# Voltmeter_schematic.net
KiCad netlist of a schematic drawn in Altium Designer
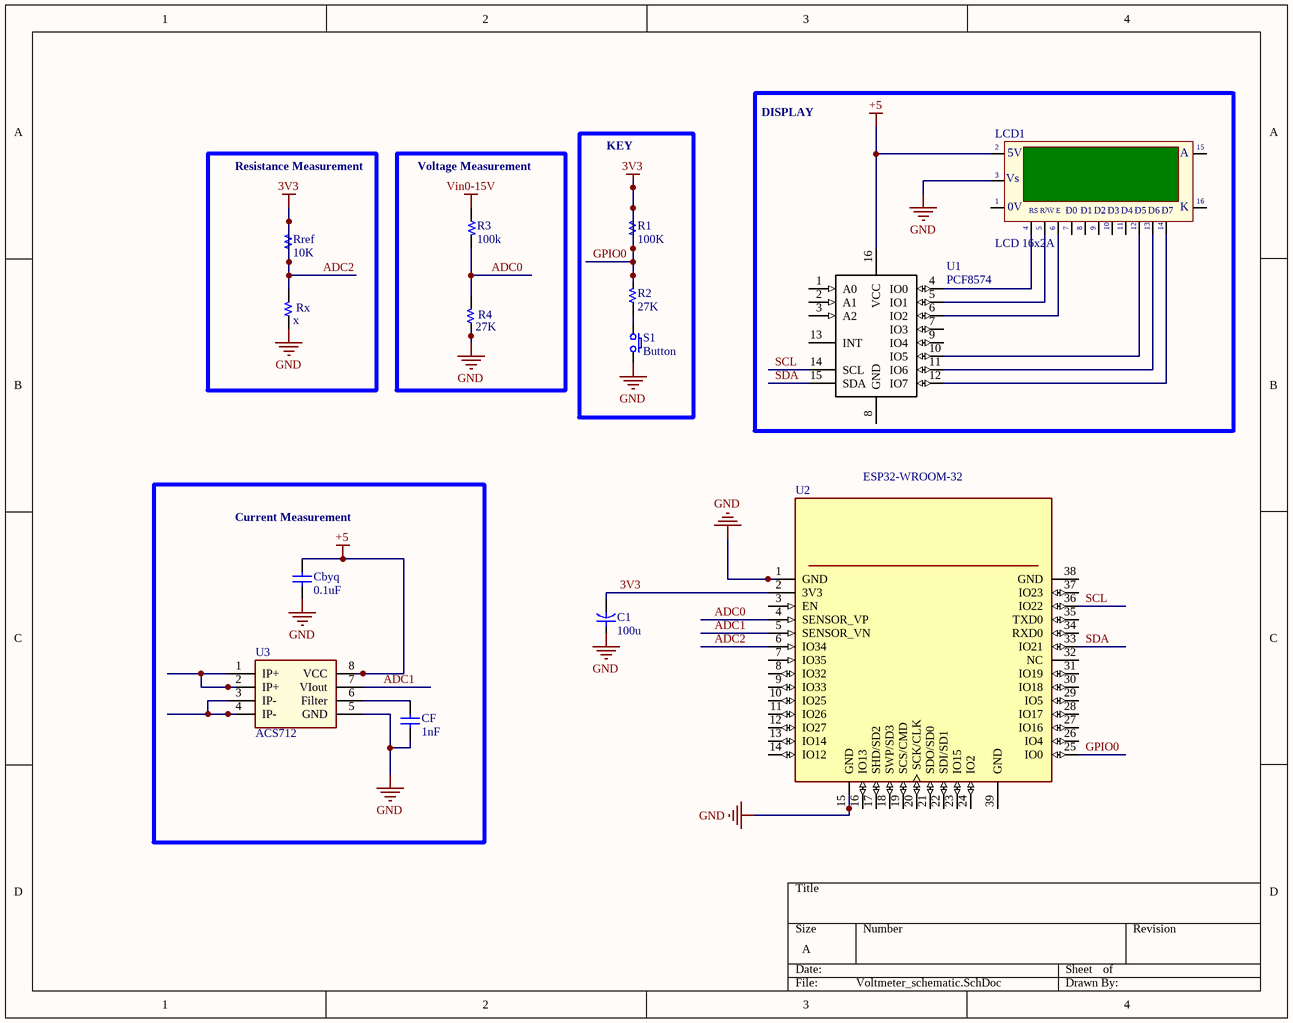
[diagram p0: Voltmeter_schematic.SchDoc]

(export (version "E")
  (design (tool "Eeschema 10.0.6"))
  (components
    (comp (ref "C1")
      (value "100u")
      (footprint "C Super Case A")
      (description "Capacitor pol")
      (libsource (lib "chipfc_libs") (part "Capacitor"))
    )
    (comp (ref "Cbyq")
      (value "0.1uF")
      (footprint "C 0805")
      (description "Capacitor non-pol")
      (libsource (lib "chipfc_libs") (part "Capacitor NP"))
    )
    (comp (ref "CF")
      (value "1nF")
      (footprint "C 0805")
      (description "Capacitor non-pol")
      (libsource (lib "chipfc_libs") (part "Capacitor NP"))
    )
    (comp (ref "LCD1")
      (value "LCD 16x2A")
      (footprint "JP16-C1T")
      (description "LCD dipslay 16 char, 2 line")
      (libsource (lib "LIBRARY") (part "LCD16x2A"))
    )
    (comp (ref "R1")
      (value "100K")
      (footprint "R 0805")
      (description "Resistor")
      (libsource (lib "chipfc_libs") (part "Resistor"))
    )
    (comp (ref "R2")
      (value "27K")
      (footprint "R 0805")
      (description "Resistor")
      (libsource (lib "chipfc_libs") (part "Resistor"))
    )
    (comp (ref "R3")
      (value "100k")
      (footprint "R 0805")
      (description "Resistor")
      (libsource (lib "chipfc_libs") (part "Resistor"))
    )
    (comp (ref "R4")
      (value "27K")
      (footprint "R 0805")
      (description "Resistor")
      (libsource (lib "chipfc_libs") (part "Resistor"))
    )
    (comp (ref "Rref")
      (value "10K")
      (footprint "R 0805")
      (description "Resistor")
      (libsource (lib "chipfc_libs") (part "Resistor"))
    )
    (comp (ref "Rx")
      (value "x")
      (footprint "R 0805")
      (description "Resistor")
      (libsource (lib "chipfc_libs") (part "Resistor"))
    )
    (comp (ref "S1")
      (value "Button")
      (footprint "SW/2/DIP")
      (description "Tact switch 2 pin")
      (libsource (lib "chipfc_libs") (part "SW SPST"))
    )
    (comp (ref "U1")
      (value "PCF8574")
      (footprint "DIP16")
      (description "I2C PORT EXPANDER")
      (fields
        (field (name "MANUFACTURER PART NUMBER") "PCF8574T/3,512")
        (field (name "MANUFACTURER") "NXP Semiconductors")
      )
      (libsource (lib "LIBRARY") (part "PCF8574"))
    )
    (comp (ref "U2")
      (value "ESP32-WROOM-32")
      (footprint "MODULE_ESP32-WROOM-32")
      (fields (field (name "MF") "Espressif Systems") (field (name "MP") "ESP32-WROOM-32D"))
      (libsource (lib "ESP32") (part "ESP32-WROOM-32"))
    )
    (comp (ref "U3") (value "ACS712") (footprint "SOIC-8") (libsource (lib "chipfc_libs") (part "ACS712")))
  )
  (nets
    (net (code "1") (name "+5") (class "Default")
      (node (ref "Cbyq") (pin "1") (pinfunction "1_1") (pintype "passive"))
      (node (ref "LCD1") (pin "2") (pinfunction "VDD_2") (pintype "passive"))
      (node (ref "U1") (pin "16") (pinfunction "VCC_16") (pintype "passive"))
      (node (ref "U3") (pin "8") (pinfunction "VCC_8") (pintype "passive"))
    )
    (net (code "2") (name "/ADC0") (class "Default")
      (node (ref "R3") (pin "2") (pinfunction "2_2") (pintype "passive"))
      (node (ref "R4") (pin "2") (pinfunction "2_2") (pintype "passive"))
      (node (ref "U2") (pin "4") (pinfunction "SENSOR_VP_4") (pintype "input"))
    )
    (net (code "3") (name "/ADC1") (class "Default")
      (node (ref "U2") (pin "5") (pinfunction "SENSOR_VN_5") (pintype "input"))
      (node (ref "U3") (pin "7") (pinfunction "VIout_7") (pintype "passive"))
    )
    (net (code "4") (name "/SCL") (class "Default")
      (node (ref "U1") (pin "14") (pinfunction "SCL_14") (pintype "open_collector"))
      (node (ref "U2") (pin "36") (pinfunction "IO22_36") (pintype "bidirectional"))
    )
    (net (code "5") (name "/SDA") (class "Default")
      (node (ref "U1") (pin "15") (pinfunction "SDA_15") (pintype "open_collector"))
      (node (ref "U2") (pin "33") (pinfunction "IO21_33") (pintype "bidirectional"))
    )
    (net (code "6") (name "3V3") (class "Default")
      (node (ref "C1") (pin "2") (pinfunction "2_2") (pintype "passive"))
      (node (ref "R1") (pin "1") (pinfunction "1_1") (pintype "passive"))
      (node (ref "R1") (pin "2") (pinfunction "2_2") (pintype "passive"))
      (node (ref "R2") (pin "2") (pinfunction "2_2") (pintype "passive"))
      (node (ref "Rref") (pin "1") (pinfunction "1_1") (pintype "passive"))
      (node (ref "Rref") (pin "2") (pinfunction "2_2") (pintype "passive"))
      (node (ref "Rx") (pin "2") (pinfunction "2_2") (pintype "passive"))
      (node (ref "U2") (pin "2") (pinfunction "3V3_2") (pintype "power_in"))
      (node (ref "U2") (pin "25") (pinfunction "IO0_25") (pintype "bidirectional"))
      (node (ref "U2") (pin "6") (pinfunction "IO34_6") (pintype "input"))
    )
    (net (code "7") (name "GND") (class "Default")
      (node (ref "CF") (pin "2") (pinfunction "2_2") (pintype "passive"))
      (node (ref "Cbyq") (pin "2") (pinfunction "2_2") (pintype "passive"))
      (node (ref "LCD1") (pin "3") (pinfunction "VEE_3") (pintype "passive"))
      (node (ref "R4") (pin "1") (pinfunction "1_1") (pintype "passive"))
      (node (ref "Rx") (pin "1") (pinfunction "1_1") (pintype "passive"))
      (node (ref "S1") (pin "2") (pinfunction "2_2") (pintype "passive"))
      (node (ref "U2") (pin "1") (pinfunction "GND_1") (pintype "power_in"))
      (node (ref "U2") (pin "15") (pinfunction "GND_15") (pintype "power_in"))
      (node (ref "U3") (pin "5") (pinfunction "GND_5") (pintype "passive"))
    )
    (net (code "8") (name "Net-(LCD1-D5)") (class "Default")
      (node (ref "LCD1") (pin "12") (pinfunction "D5_12") (pintype "passive"))
      (node (ref "U1") (pin "10") (pinfunction "IO5_10") (pintype "bidirectional"))
    )
    (net (code "9") (name "Net-(LCD1-D6)") (class "Default")
      (node (ref "LCD1") (pin "13") (pinfunction "D6_13") (pintype "passive"))
      (node (ref "U1") (pin "11") (pinfunction "IO6_11") (pintype "bidirectional"))
    )
    (net (code "10") (name "Net-(LCD1-D7)") (class "Default")
      (node (ref "LCD1") (pin "14") (pinfunction "D7_14") (pintype "passive"))
      (node (ref "U1") (pin "12") (pinfunction "IO7_12") (pintype "bidirectional"))
    )
    (net (code "11") (name "Net-(LCD1-RS)") (class "Default")
      (node (ref "LCD1") (pin "4") (pinfunction "RS_4") (pintype "passive"))
      (node (ref "U1") (pin "4") (pinfunction "IO0_4") (pintype "bidirectional"))
    )
    (net (code "12") (name "Net-(LCD1-R{slash}~{W})") (class "Default")
      (node (ref "LCD1") (pin "5") (pinfunction "R/~{W}_5") (pintype "passive"))
      (node (ref "U1") (pin "5") (pinfunction "IO1_5") (pintype "bidirectional"))
    )
    (net (code "13") (name "Net-(LCD1-~{EN})") (class "Default")
      (node (ref "LCD1") (pin "6") (pinfunction "~{EN}_6") (pintype "passive"))
      (node (ref "U1") (pin "6") (pinfunction "IO2_6") (pintype "bidirectional"))
    )
    (net (code "14") (name "Net-(R2-Pad1)") (class "Default")
      (node (ref "R2") (pin "1") (pinfunction "1_1") (pintype "passive"))
      (node (ref "S1") (pin "1") (pinfunction "1_1") (pintype "passive"))
    )
    (net (code "15") (name "Net-(U3-Filter)") (class "Default")
      (node (ref "CF") (pin "1") (pinfunction "1_1") (pintype "passive"))
      (node (ref "U3") (pin "6") (pinfunction "Filter_6") (pintype "passive"))
    )
    (net (code "16") (name "Net-(U3-IP+-Pad1)") (class "Default")
      (node (ref "U3") (pin "1") (pinfunction "IP+_1") (pintype "passive"))
      (node (ref "U3") (pin "2") (pinfunction "IP+_2") (pintype "passive"))
    )
    (net (code "17") (name "Net-(U3-IP--Pad3)") (class "Default")
      (node (ref "U3") (pin "3") (pinfunction "IP-_3") (pintype "passive"))
      (node (ref "U3") (pin "4") (pinfunction "IP-_4") (pintype "passive"))
    )
    (net (code "18") (name "Vin0-15V") (class "Default")
      (node (ref "R3") (pin "1") (pinfunction "1_1") (pintype "passive"))
    )
    (net (code "19") (name "unconnected-(C1-Pad1)") (class "Default")
      (node (ref "C1") (pin "1") (pinfunction "1_1") (pintype "passive"))
    )
    (net (code "20") (name "unconnected-(LCD1-A-Pad15)") (class "Default")
      (node (ref "LCD1") (pin "15") (pinfunction "A_15") (pintype "passive"))
    )
    (net (code "21") (name "unconnected-(LCD1-D0-Pad7)") (class "Default")
      (node (ref "LCD1") (pin "7") (pinfunction "D0_7") (pintype "passive"))
    )
    (net (code "22") (name "unconnected-(LCD1-D1-Pad8)") (class "Default")
      (node (ref "LCD1") (pin "8") (pinfunction "D1_8") (pintype "passive"))
    )
    (net (code "23") (name "unconnected-(LCD1-D2-Pad9)") (class "Default")
      (node (ref "LCD1") (pin "9") (pinfunction "D2_9") (pintype "passive"))
    )
    (net (code "24") (name "unconnected-(LCD1-D3-Pad10)") (class "Default")
      (node (ref "LCD1") (pin "10") (pinfunction "D3_10") (pintype "passive"))
    )
    (net (code "25") (name "unconnected-(LCD1-D4-Pad11)") (class "Default")
      (node (ref "LCD1") (pin "11") (pinfunction "D4_11") (pintype "passive"))
    )
    (net (code "26") (name "unconnected-(LCD1-GND-Pad1)") (class "Default")
      (node (ref "LCD1") (pin "1") (pinfunction "GND_1") (pintype "passive"))
    )
    (net (code "27") (name "unconnected-(LCD1-K-Pad16)") (class "Default")
      (node (ref "LCD1") (pin "16") (pinfunction "K_16") (pintype "passive"))
    )
    (net (code "28") (name "unconnected-(U1-A0-Pad1)") (class "Default")
      (node (ref "U1") (pin "1") (pinfunction "A0_1") (pintype "input"))
    )
    (net (code "29") (name "unconnected-(U1-A1-Pad2)") (class "Default")
      (node (ref "U1") (pin "2") (pinfunction "A1_2") (pintype "input"))
    )
    (net (code "30") (name "unconnected-(U1-A2-Pad3)") (class "Default")
      (node (ref "U1") (pin "3") (pinfunction "A2_3") (pintype "input"))
    )
    (net (code "31") (name "unconnected-(U1-GND-Pad8)") (class "Default")
      (node (ref "U1") (pin "8") (pinfunction "GND_8") (pintype "open_collector"))
    )
    (net (code "32") (name "unconnected-(U1-INT-Pad13)") (class "Default")
      (node (ref "U1") (pin "13") (pinfunction "INT_13") (pintype "open_collector"))
    )
    (net (code "33") (name "unconnected-(U1-IO3-Pad7)") (class "Default")
      (node (ref "U1") (pin "7") (pinfunction "IO3_7") (pintype "bidirectional"))
    )
    (net (code "34") (name "unconnected-(U1-IO4-Pad9)") (class "Default")
      (node (ref "U1") (pin "9") (pinfunction "IO4_9") (pintype "bidirectional"))
    )
    (net (code "35") (name "unconnected-(U2-EN-Pad3)") (class "Default")
      (node (ref "U2") (pin "3") (pinfunction "EN_3") (pintype "input"))
    )
    (net (code "36") (name "unconnected-(U2-GND-Pad38)") (class "Default")
      (node (ref "U2") (pin "38") (pinfunction "GND_38") (pintype "power_in"))
    )
    (net (code "37") (name "unconnected-(U2-GND-Pad39)") (class "Default")
      (node (ref "U2") (pin "39") (pinfunction "GND_39") (pintype "power_in"))
    )
    (net (code "38") (name "unconnected-(U2-IO2-Pad24)") (class "Default")
      (node (ref "U2") (pin "24") (pinfunction "IO2_24") (pintype "bidirectional"))
    )
    (net (code "39") (name "unconnected-(U2-IO4-Pad26)") (class "Default")
      (node (ref "U2") (pin "26") (pinfunction "IO4_26") (pintype "bidirectional"))
    )
    (net (code "40") (name "unconnected-(U2-IO5-Pad29)") (class "Default")
      (node (ref "U2") (pin "29") (pinfunction "IO5_29") (pintype "bidirectional"))
    )
    (net (code "41") (name "unconnected-(U2-IO12-Pad14)") (class "Default")
      (node (ref "U2") (pin "14") (pinfunction "IO12_14") (pintype "bidirectional"))
    )
    (net (code "42") (name "unconnected-(U2-IO13-Pad16)") (class "Default")
      (node (ref "U2") (pin "16") (pinfunction "IO13_16") (pintype "bidirectional"))
    )
    (net (code "43") (name "unconnected-(U2-IO14-Pad13)") (class "Default")
      (node (ref "U2") (pin "13") (pinfunction "IO14_13") (pintype "bidirectional"))
    )
    (net (code "44") (name "unconnected-(U2-IO15-Pad23)") (class "Default")
      (node (ref "U2") (pin "23") (pinfunction "IO15_23") (pintype "bidirectional"))
    )
    (net (code "45") (name "unconnected-(U2-IO16-Pad27)") (class "Default")
      (node (ref "U2") (pin "27") (pinfunction "IO16_27") (pintype "bidirectional"))
    )
    (net (code "46") (name "unconnected-(U2-IO17-Pad28)") (class "Default")
      (node (ref "U2") (pin "28") (pinfunction "IO17_28") (pintype "bidirectional"))
    )
    (net (code "47") (name "unconnected-(U2-IO18-Pad30)") (class "Default")
      (node (ref "U2") (pin "30") (pinfunction "IO18_30") (pintype "bidirectional"))
    )
    (net (code "48") (name "unconnected-(U2-IO19-Pad31)") (class "Default")
      (node (ref "U2") (pin "31") (pinfunction "IO19_31") (pintype "bidirectional"))
    )
    (net (code "49") (name "unconnected-(U2-IO23-Pad37)") (class "Default")
      (node (ref "U2") (pin "37") (pinfunction "IO23_37") (pintype "bidirectional"))
    )
    (net (code "50") (name "unconnected-(U2-IO25-Pad10)") (class "Default")
      (node (ref "U2") (pin "10") (pinfunction "IO25_10") (pintype "bidirectional"))
    )
    (net (code "51") (name "unconnected-(U2-IO26-Pad11)") (class "Default")
      (node (ref "U2") (pin "11") (pinfunction "IO26_11") (pintype "bidirectional"))
    )
    (net (code "52") (name "unconnected-(U2-IO27-Pad12)") (class "Default")
      (node (ref "U2") (pin "12") (pinfunction "IO27_12") (pintype "bidirectional"))
    )
    (net (code "53") (name "unconnected-(U2-IO32-Pad8)") (class "Default")
      (node (ref "U2") (pin "8") (pinfunction "IO32_8") (pintype "bidirectional"))
    )
    (net (code "54") (name "unconnected-(U2-IO33-Pad9)") (class "Default")
      (node (ref "U2") (pin "9") (pinfunction "IO33_9") (pintype "bidirectional"))
    )
    (net (code "55") (name "unconnected-(U2-IO35-Pad7)") (class "Default")
      (node (ref "U2") (pin "7") (pinfunction "IO35_7") (pintype "input"))
    )
    (net (code "56") (name "unconnected-(U2-NC-Pad32)") (class "Default")
      (node (ref "U2") (pin "32") (pinfunction "NC_32") (pintype "power_in"))
    )
    (net (code "57") (name "unconnected-(U2-RXD0-Pad34)") (class "Default")
      (node (ref "U2") (pin "34") (pinfunction "RXD0_34") (pintype "bidirectional"))
    )
    (net (code "58") (name "unconnected-(U2-SCK{slash}CLK-Pad20)") (class "Default")
      (node (ref "U2") (pin "20") (pinfunction "SCK/CLK_20") (pintype "bidirectional"))
    )
    (net (code "59") (name "unconnected-(U2-SCS{slash}CMD-Pad19)") (class "Default")
      (node (ref "U2") (pin "19") (pinfunction "SCS/CMD_19") (pintype "bidirectional"))
    )
    (net (code "60") (name "unconnected-(U2-SDI{slash}SD1-Pad22)") (class "Default")
      (node (ref "U2") (pin "22") (pinfunction "SDI/SD1_22") (pintype "bidirectional"))
    )
    (net (code "61") (name "unconnected-(U2-SDO{slash}SD0-Pad21)") (class "Default")
      (node (ref "U2") (pin "21") (pinfunction "SDO/SD0_21") (pintype "bidirectional"))
    )
    (net (code "62") (name "unconnected-(U2-SHD{slash}SD2-Pad17)") (class "Default")
      (node (ref "U2") (pin "17") (pinfunction "SHD/SD2_17") (pintype "bidirectional"))
    )
    (net (code "63") (name "unconnected-(U2-SWP{slash}SD3-Pad18)") (class "Default")
      (node (ref "U2") (pin "18") (pinfunction "SWP/SD3_18") (pintype "bidirectional"))
    )
    (net (code "64") (name "unconnected-(U2-TXD0-Pad35)") (class "Default")
      (node (ref "U2") (pin "35") (pinfunction "TXD0_35") (pintype "bidirectional"))
    )
  )
)
